# Controller.net
KiCad netlist of a schematic drawn in Altium Designer
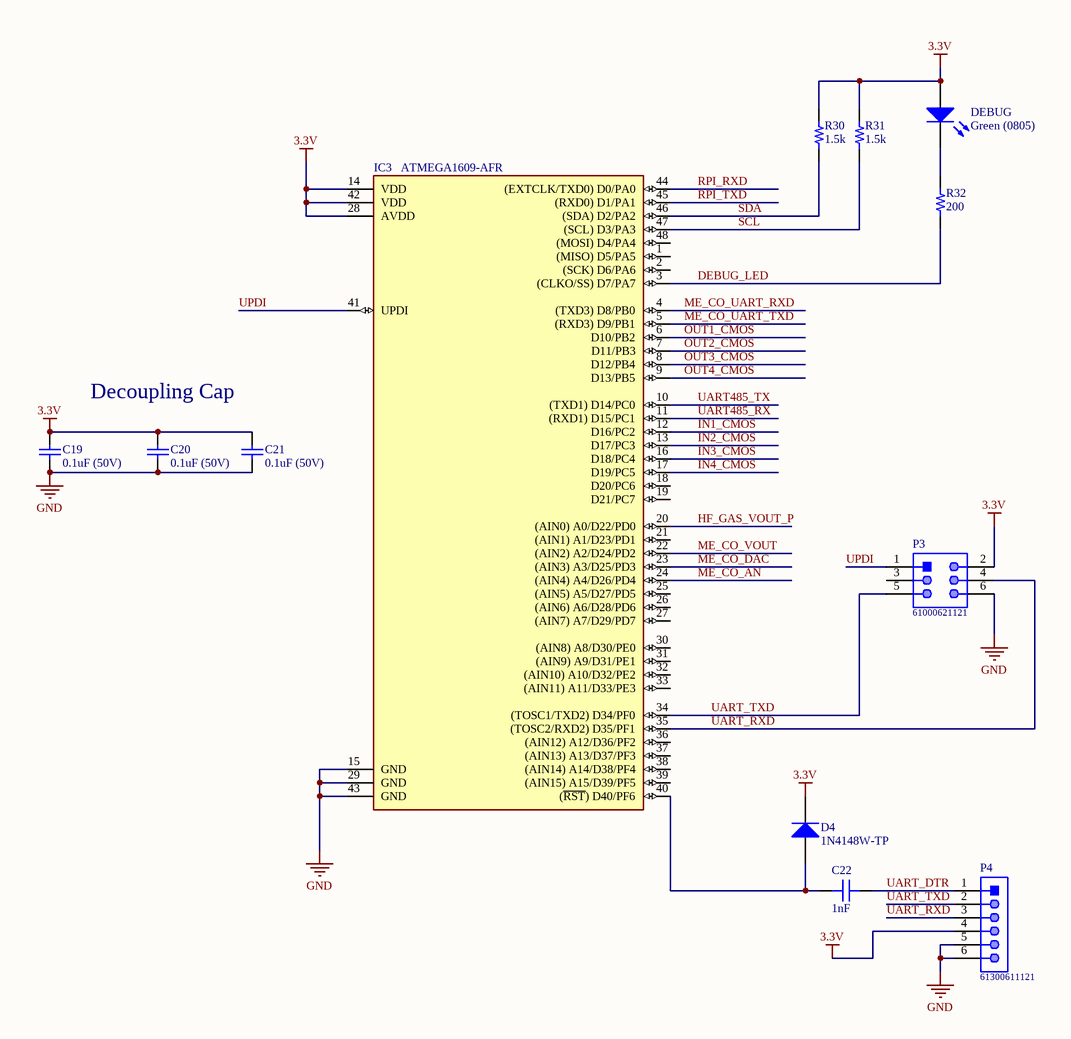
[diagram p0: Controller.SchDoc]

(export (version "E")
  (design (tool "Eeschema 10.0.6"))
  (components
    (comp (ref "C19")
      (value "0.1uF (50V)")
      (footprint "CAPC1608X95X40NL15T15")
      (fields (field (name "PART NUMBER") "VJ0603Y332JXACW1BC") (field (name "MANUFACTURER") "Vitramon"))
      (libsource (lib "Altium Content Vault") (part "CAP"))
    )
    (comp (ref "C20")
      (value "0.1uF (50V)")
      (footprint "CAPC1608X95X40NL15T15")
      (fields (field (name "PART NUMBER") "VJ0603Y332JXACW1BC") (field (name "MANUFACTURER") "Vitramon"))
      (libsource (lib "Altium Content Vault") (part "CAP"))
    )
    (comp (ref "C21")
      (value "0.1uF (50V)")
      (footprint "CAPC1608X95X40NL15T15")
      (fields (field (name "PART NUMBER") "VJ0603Y332JXACW1BC") (field (name "MANUFACTURER") "Vitramon"))
      (libsource (lib "Altium Content Vault") (part "CAP"))
    )
    (comp (ref "C22")
      (value "1nF")
      (footprint "CAP 0603_1608")
      (description "CAP CERAMIC 50V X7R 0603")
      (fields
        (field (name "PART NUMBER") "VJ0603Y332JXACW1BC")
        (field (name "MANUFACTURER") "Vishay Vitramon")
      )
      (libsource (lib "Celestial Altium Library - altium_library") (part "Capacitor"))
    )
    (comp (ref "D4")
      (value "1N4148W-TP")
      (footprint "MCC-SOD123_V")
      (description "High Speed Switching Diode, 400 mW, 150 mA, -65 to 150 degC, 2-Pin SOD123, RoHS, Tape and Reel")
      (fields (field (name "MANUFACTURER") "Micro Commercial Components"))
      (libsource (lib "Altium Content Vault") (part "D-AK-2"))
    )
    (comp (ref "DEBUG")
      (value "Green (0805)")
      (footprint "0805_A")
      (description "SMD mono-color Chip LED, WL-SMCW, Green")
      (fields (field (name "PARTNUMBER") "150080GS75000") (field (name "MANUFACTURER") "Wuerth Elektronik"))
      (libsource (lib "Altium Content Vault") (part "WE-LED_K1A2-2"))
    )
    (comp (ref "IC3")
      (value "ATMEGA1609-AFR")
      (footprint "SamacSys:QFP50P900X900X120-48N")
      (description "Integrated Circuit")
      (fields (field (name "MOUSER PART NUMBER") "579-ATMEGA1609-AFR"))
      (libsource (lib "SamacSys") (part "ATMEGA1609-AFR"))
    )
    (comp (ref "P3")
      (value "61000621121")
      (footprint "61000621121")
      (description "SMT Vertical Pin Header WR-PHD, Pitch 2.54 mm, Dual Row, 6 pins")
      (fields (field (name "MANUFACTURER") "Wurth Elektronik") (field (name "PUBLISHER") "WurthElektronik"))
      (libsource (lib "Altium Content Vault") (part "WE-CN-2P-M-R6"))
    )
    (comp (ref "P4")
      (value "61300611121")
      (footprint "61300611121")
      (description "THT Vertical Pin Header WR-PHD, Pitch 2.54 mm, Single Row, 6 pins")
      (fields (field (name "MANUFACTURER") "Wurth Elektronik") (field (name "PUBLISHER") "WurthElektronik"))
      (libsource (lib "Altium Content Vault") (part "WE-CN-1P-M-R6"))
    )
    (comp (ref "R30")
      (value "1.5k")
      (footprint "RES 0603_1608")
      (description "Resistor")
      (fields (field (name "PART NUMBER") "CRCW060329K4FKEA") (field (name "MANUFACTURER") "Vishay Dale"))
      (libsource (lib "Celestial Altium Library - altium_library") (part "Resistor"))
    )
    (comp (ref "R31")
      (value "1.5k")
      (footprint "RES 0603_1608")
      (description "Resistor")
      (fields (field (name "PART NUMBER") "CRCW060329K4FKEA") (field (name "MANUFACTURER") "Vishay Dale"))
      (libsource (lib "Celestial Altium Library - altium_library") (part "Resistor"))
    )
    (comp (ref "R32")
      (value "200")
      (footprint "RES 0603_1608")
      (description "Resistor")
      (fields (field (name "PART NUMBER") "CRCW060329K4FKEA") (field (name "MANUFACTURER") "Vishay Dale"))
      (libsource (lib "Celestial Altium Library - altium_library") (part "Resistor"))
    )
  )
  (nets
    (net (code "1") (name "/DEBUG_LED") (class "Default")
      (node (ref "IC3") (pin "3") (pinfunction "(CLKO/SS)_D7/PA7_3") (pintype "bidirectional"))
      (node (ref "R32") (pin "1") (pinfunction "1_1") (pintype "passive"))
    )
    (net (code "2") (name "/HF_GAS_VOUT_P") (class "Default")
      (node (ref "IC3") (pin "20") (pinfunction "(AIN0)_A0/D22/PD0_20") (pintype "bidirectional"))
    )
    (net (code "3") (name "/IN1_CMOS") (class "Default")
      (node (ref "IC3") (pin "12") (pinfunction "D16/PC2_12") (pintype "bidirectional"))
    )
    (net (code "4") (name "/IN2_CMOS") (class "Default")
      (node (ref "IC3") (pin "13") (pinfunction "D17/PC3_13") (pintype "bidirectional"))
    )
    (net (code "5") (name "/IN3_CMOS") (class "Default")
      (node (ref "IC3") (pin "16") (pinfunction "D18/PC4_16") (pintype "bidirectional"))
    )
    (net (code "6") (name "/IN4_CMOS") (class "Default")
      (node (ref "IC3") (pin "17") (pinfunction "D19/PC5_17") (pintype "bidirectional"))
    )
    (net (code "7") (name "/ME_CO_AN") (class "Default")
      (node (ref "IC3") (pin "24") (pinfunction "(AIN4)_A4/D26/PD4_24") (pintype "bidirectional"))
    )
    (net (code "8") (name "/ME_CO_DAC") (class "Default")
      (node (ref "IC3") (pin "23") (pinfunction "(AIN3)_A3/D25/PD3_23") (pintype "bidirectional"))
    )
    (net (code "9") (name "/ME_CO_UART_RXD") (class "Default")
      (node (ref "IC3") (pin "4") (pinfunction "(TXD3)_D8/PB0_4") (pintype "bidirectional"))
    )
    (net (code "10") (name "/ME_CO_UART_TXD") (class "Default")
      (node (ref "IC3") (pin "5") (pinfunction "(RXD3)_D9/PB1_5") (pintype "bidirectional"))
    )
    (net (code "11") (name "/ME_CO_VOUT") (class "Default")
      (node (ref "IC3") (pin "22") (pinfunction "(AIN2)_A2/D24/PD2_22") (pintype "bidirectional"))
    )
    (net (code "12") (name "/OUT1_CMOS") (class "Default")
      (node (ref "IC3") (pin "6") (pinfunction "D10/PB2_6") (pintype "bidirectional"))
    )
    (net (code "13") (name "/OUT2_CMOS") (class "Default")
      (node (ref "IC3") (pin "7") (pinfunction "D11/PB3_7") (pintype "bidirectional"))
    )
    (net (code "14") (name "/OUT3_CMOS") (class "Default")
      (node (ref "IC3") (pin "8") (pinfunction "D12/PB4_8") (pintype "bidirectional"))
    )
    (net (code "15") (name "/OUT4_CMOS") (class "Default")
      (node (ref "IC3") (pin "9") (pinfunction "D13/PB5_9") (pintype "bidirectional"))
    )
    (net (code "16") (name "/RPI_RXD") (class "Default")
      (node (ref "IC3") (pin "44") (pinfunction "(EXTCLK/TXD0)_D0/PA0_44") (pintype "bidirectional"))
    )
    (net (code "17") (name "/RPI_TXD") (class "Default")
      (node (ref "IC3") (pin "45") (pinfunction "(RXD0)_D1/PA1_45") (pintype "bidirectional"))
    )
    (net (code "18") (name "/SCL") (class "Default")
      (node (ref "IC3") (pin "47") (pinfunction "(SCL)_D3/PA3_47") (pintype "bidirectional"))
      (node (ref "R31") (pin "2") (pinfunction "2_2") (pintype "passive"))
    )
    (net (code "19") (name "/SDA") (class "Default")
      (node (ref "IC3") (pin "46") (pinfunction "(SDA)_D2/PA2_46") (pintype "bidirectional"))
      (node (ref "R30") (pin "2") (pinfunction "2_2") (pintype "passive"))
    )
    (net (code "20") (name "/UART485_RX") (class "Default")
      (node (ref "IC3") (pin "11") (pinfunction "(RXD1)_D15/PC1_11") (pintype "bidirectional"))
    )
    (net (code "21") (name "/UART485_TX") (class "Default")
      (node (ref "IC3") (pin "10") (pinfunction "(TXD1)_D14/PC0_10") (pintype "bidirectional"))
    )
    (net (code "22") (name "/UART_DTR") (class "Default")
      (node (ref "C22") (pin "1") (pinfunction "1_1") (pintype "passive"))
      (node (ref "P4") (pin "1") (pinfunction "1_1") (pintype "passive"))
    )
    (net (code "23") (name "/UART_RXD") (class "Default")
      (node (ref "IC3") (pin "35") (pinfunction "(TOSC2/RXD2)_D35/PF1_35") (pintype "bidirectional"))
      (node (ref "P3") (pin "4") (pinfunction "4_4") (pintype "passive"))
      (node (ref "P4") (pin "3") (pinfunction "3_3") (pintype "passive"))
    )
    (net (code "24") (name "/UART_TXD") (class "Default")
      (node (ref "IC3") (pin "34") (pinfunction "(TOSC1/TXD2)_D34/PF0_34") (pintype "bidirectional"))
      (node (ref "P3") (pin "5") (pinfunction "5_5") (pintype "passive"))
      (node (ref "P4") (pin "2") (pinfunction "2_2") (pintype "passive"))
    )
    (net (code "25") (name "/UPDI") (class "Default")
      (node (ref "IC3") (pin "41") (pinfunction "UPDI_41") (pintype "bidirectional"))
      (node (ref "P3") (pin "1") (pinfunction "1_1") (pintype "passive"))
    )
    (net (code "26") (name "3.3V") (class "Default")
      (node (ref "C19") (pin "2") (pinfunction "2_2") (pintype "passive"))
      (node (ref "C20") (pin "2") (pinfunction "2_2") (pintype "passive"))
      (node (ref "C21") (pin "2") (pinfunction "2_2") (pintype "passive"))
      (node (ref "D4") (pin "2") (pinfunction "K_2") (pintype "passive"))
      (node (ref "DEBUG") (pin "2") (pinfunction "A_2") (pintype "passive"))
      (node (ref "IC3") (pin "14") (pinfunction "VDD_14") (pintype "power_in"))
      (node (ref "IC3") (pin "28") (pinfunction "AVDD_28") (pintype "power_in"))
      (node (ref "IC3") (pin "42") (pinfunction "VDD_42") (pintype "power_in"))
      (node (ref "P3") (pin "2") (pinfunction "2_2") (pintype "passive"))
      (node (ref "P4") (pin "4") (pinfunction "4_4") (pintype "passive"))
      (node (ref "R30") (pin "1") (pinfunction "1_1") (pintype "passive"))
      (node (ref "R31") (pin "1") (pinfunction "1_1") (pintype "passive"))
    )
    (net (code "27") (name "GND") (class "Default")
      (node (ref "C19") (pin "1") (pinfunction "1_1") (pintype "passive"))
      (node (ref "C20") (pin "1") (pinfunction "1_1") (pintype "passive"))
      (node (ref "C21") (pin "1") (pinfunction "1_1") (pintype "passive"))
      (node (ref "IC3") (pin "15") (pinfunction "GND_15") (pintype "power_in"))
      (node (ref "IC3") (pin "29") (pinfunction "GND_29") (pintype "power_in"))
      (node (ref "IC3") (pin "43") (pinfunction "GND_43") (pintype "power_in"))
      (node (ref "P3") (pin "6") (pinfunction "6_6") (pintype "passive"))
      (node (ref "P4") (pin "5") (pinfunction "5_5") (pintype "passive"))
      (node (ref "P4") (pin "6") (pinfunction "6_6") (pintype "passive"))
    )
    (net (code "28") (name "Net-(D4-A)") (class "Default")
      (node (ref "C22") (pin "2") (pinfunction "2_2") (pintype "passive"))
      (node (ref "D4") (pin "1") (pinfunction "A_1") (pintype "passive"))
      (node (ref "IC3") (pin "40") (pinfunction "(~{RST})_D40/PF6_40") (pintype "bidirectional"))
    )
    (net (code "29") (name "Net-(DEBUG-K)") (class "Default")
      (node (ref "DEBUG") (pin "1") (pinfunction "K_1") (pintype "passive"))
      (node (ref "R32") (pin "2") (pinfunction "2_2") (pintype "passive"))
    )
    (net (code "30") (name "unconnected-(IC3-(AIN1)_A1{slash}D23{slash}PD1-Pad21)") (class "Default")
      (node (ref "IC3") (pin "21") (pinfunction "(AIN1)_A1/D23/PD1_21") (pintype "bidirectional"))
    )
    (net (code "31") (name "unconnected-(IC3-(AIN5)_A5{slash}D27{slash}PD5-Pad25)") (class "Default")
      (node (ref "IC3") (pin "25") (pinfunction "(AIN5)_A5/D27/PD5_25") (pintype "bidirectional"))
    )
    (net (code "32") (name "unconnected-(IC3-(AIN6)_A6{slash}D28{slash}PD6-Pad26)") (class "Default")
      (node (ref "IC3") (pin "26") (pinfunction "(AIN6)_A6/D28/PD6_26") (pintype "bidirectional"))
    )
    (net (code "33") (name "unconnected-(IC3-(AIN7)_A7{slash}D29{slash}PD7-Pad27)") (class "Default")
      (node (ref "IC3") (pin "27") (pinfunction "(AIN7)_A7/D29/PD7_27") (pintype "bidirectional"))
    )
    (net (code "34") (name "unconnected-(IC3-(AIN8)_A8{slash}D30{slash}PE0-Pad30)") (class "Default")
      (node (ref "IC3") (pin "30") (pinfunction "(AIN8)_A8/D30/PE0_30") (pintype "bidirectional"))
    )
    (net (code "35") (name "unconnected-(IC3-(AIN9)_A9{slash}D31{slash}PE1-Pad31)") (class "Default")
      (node (ref "IC3") (pin "31") (pinfunction "(AIN9)_A9/D31/PE1_31") (pintype "bidirectional"))
    )
    (net (code "36") (name "unconnected-(IC3-(AIN10)_A10{slash}D32{slash}PE2-Pad32)") (class "Default")
      (node (ref "IC3") (pin "32") (pinfunction "(AIN10)_A10/D32/PE2_32") (pintype "bidirectional"))
    )
    (net (code "37") (name "unconnected-(IC3-(AIN11)_A11{slash}D33{slash}PE3-Pad33)") (class "Default")
      (node (ref "IC3") (pin "33") (pinfunction "(AIN11)_A11/D33/PE3_33") (pintype "bidirectional"))
    )
    (net (code "38") (name "unconnected-(IC3-(AIN12)_A12{slash}D36{slash}PF2-Pad36)") (class "Default")
      (node (ref "IC3") (pin "36") (pinfunction "(AIN12)_A12/D36/PF2_36") (pintype "bidirectional"))
    )
    (net (code "39") (name "unconnected-(IC3-(AIN13)_A13{slash}D37{slash}PF3-Pad37)") (class "Default")
      (node (ref "IC3") (pin "37") (pinfunction "(AIN13)_A13/D37/PF3_37") (pintype "bidirectional"))
    )
    (net (code "40") (name "unconnected-(IC3-(AIN14)_A14{slash}D38{slash}PF4-Pad38)") (class "Default")
      (node (ref "IC3") (pin "38") (pinfunction "(AIN14)_A14/D38/PF4_38") (pintype "bidirectional"))
    )
    (net (code "41") (name "unconnected-(IC3-(AIN15)_A15{slash}D39{slash}PF5-Pad39)") (class "Default")
      (node (ref "IC3") (pin "39") (pinfunction "(AIN15)_A15/D39/PF5_39") (pintype "bidirectional"))
    )
    (net (code "42") (name "unconnected-(IC3-(MISO)_D5{slash}PA5-Pad1)") (class "Default")
      (node (ref "IC3") (pin "1") (pinfunction "(MISO)_D5/PA5_1") (pintype "bidirectional"))
    )
    (net (code "43") (name "unconnected-(IC3-(MOSI)_D4{slash}PA4-Pad48)") (class "Default")
      (node (ref "IC3") (pin "48") (pinfunction "(MOSI)_D4/PA4_48") (pintype "bidirectional"))
    )
    (net (code "44") (name "unconnected-(IC3-(SCK)_D6{slash}PA6-Pad2)") (class "Default")
      (node (ref "IC3") (pin "2") (pinfunction "(SCK)_D6/PA6_2") (pintype "bidirectional"))
    )
    (net (code "45") (name "unconnected-(IC3-D20{slash}PC6-Pad18)") (class "Default")
      (node (ref "IC3") (pin "18") (pinfunction "D20/PC6_18") (pintype "bidirectional"))
    )
    (net (code "46") (name "unconnected-(IC3-D21{slash}PC7-Pad19)") (class "Default")
      (node (ref "IC3") (pin "19") (pinfunction "D21/PC7_19") (pintype "bidirectional"))
    )
    (net (code "47") (name "unconnected-(P3-Pad3)") (class "Default")
      (node (ref "P3") (pin "3") (pinfunction "3_3") (pintype "passive"))
    )
  )
)
